# DownLoad.net
KiCad netlist of a schematic drawn in Altium Designer
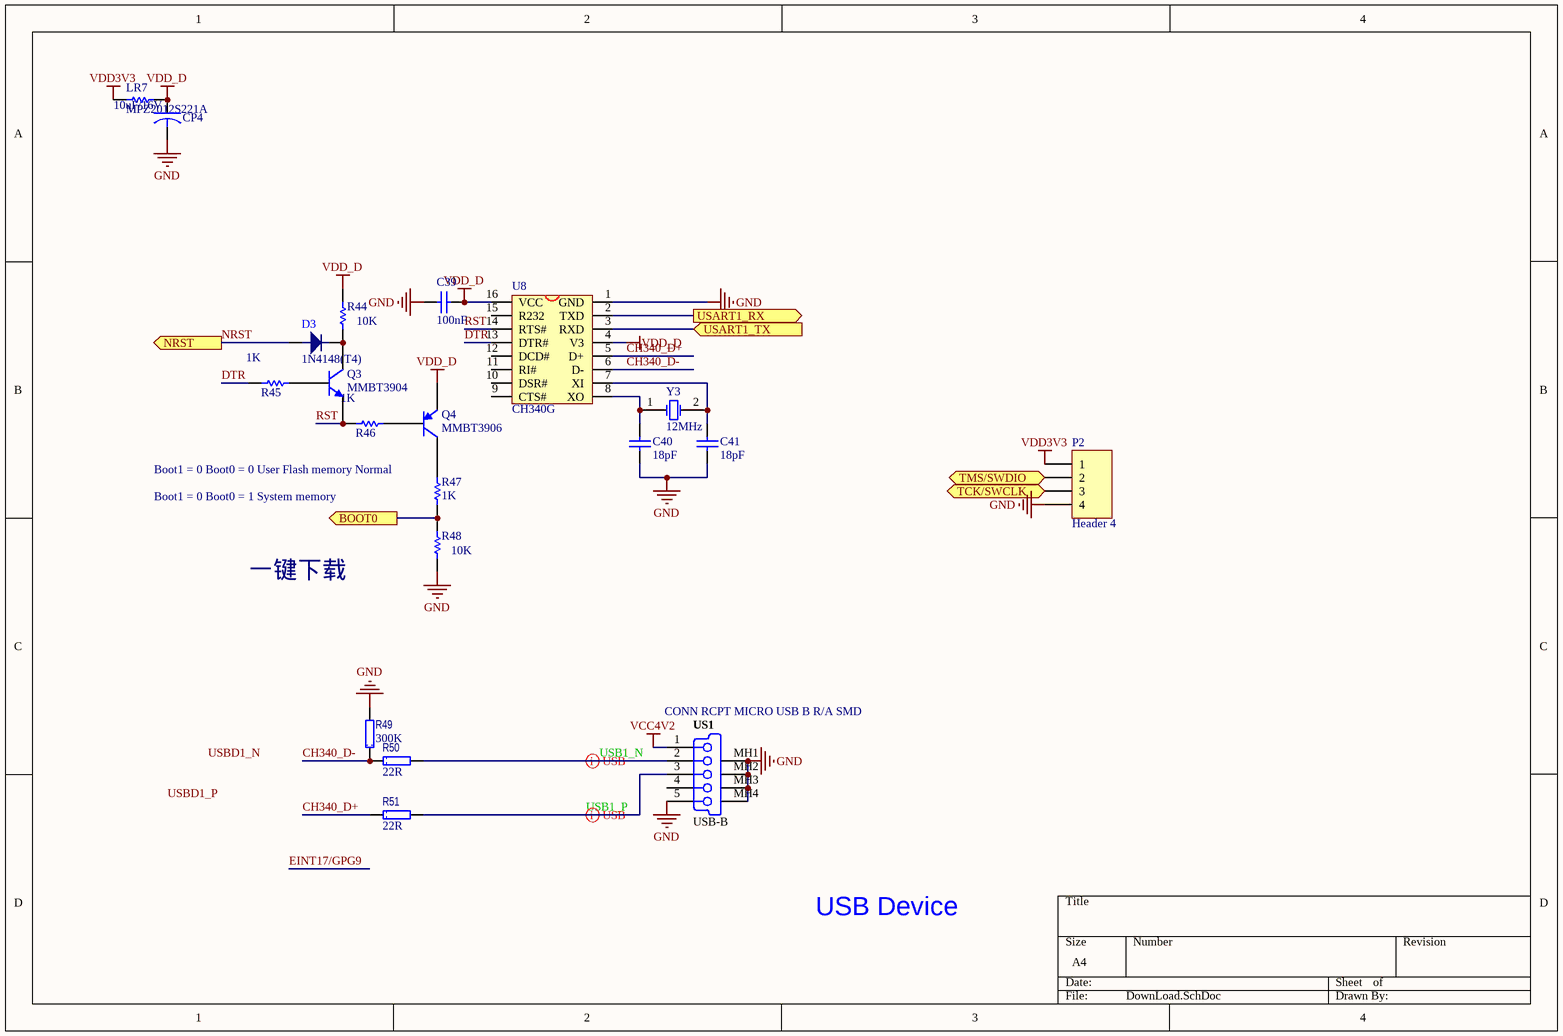
[diagram p0: DownLoad.SchDoc]

(export (version "E")
  (design (tool "Eeschema 10.0.6"))
  (components
    (comp (ref "C39")
      (value "100nF")
      (footprint "2012[0805]06CD")
      (description "CAP 100nF 50V ±5% 0805 (2012 Metric) Thickness 1mm SMD")
      (fields (field (name "TOLERANCE") "±5%") (field (name "Comment") "CAP 100nF 50V 0805(2012)"))
      (libsource (lib "Altium Content Vault") (part "CMP-1036-04418-1"))
    )
    (comp (ref "C40")
      (value "18pF")
      (footprint "2012[0805]100_L")
      (description "CAP 18pF 50V ±1% 0805 (2012 Metric) Thickness 0.75mm SMD")
      (fields (field (name "TOLERANCE") "±1%") (field (name "Comment") "CAP 18pF 50V 0805(2012)"))
      (libsource (lib "Altium Content Vault") (part "CMP-1036-01136-1"))
    )
    (comp (ref "C41")
      (value "18pF")
      (footprint "2012[0805]100_L")
      (description "CAP 18pF 50V ±1% 0805 (2012 Metric) Thickness 0.75mm SMD")
      (fields (field (name "TOLERANCE") "±1%") (field (name "Comment") "CAP 18pF 50V 0805(2012)"))
      (libsource (lib "Altium Content Vault") (part "CMP-1036-01136-1"))
    )
    (comp (ref "CP4")
      (value "10uF/16V")
      (footprint "3216[1206]CB")
      (description "钽质电容器-固体SMD 16volts 10uF 10%")
      (fields (field (name "MANUFACTURER") "AVX") (field (name "MANUFACTURER PART NUMBER") "TAJA106K016RNJ"))
      (libsource (lib "*") (part "CAPACITOR"))
    )
    (comp (ref "D3")
      (value "1N4148(T4)")
      (footprint "SOD123")
      (description "高速开关二极管")
      (libsource (lib "mylib") (part "1N4148"))
    )
    (comp (ref "LR7")
      (value "MPZ2012S221A")
      (footprint "2012[0805]RL")
      (description "电磁干扰滤波珠子、扼流圈和阵列 Ferrite Chip Beads")
      (fields (field (name "MANUFACTURER") "TDK"))
      (libsource (lib "Miscellaneous Devices") (part "Res Semi"))
    )
    (comp (ref "P2")
      (value "Header 4")
      (footprint "HDR1X4")
      (description "Header, 4-Pin")
      (fields (field (name "PUBLISHER") "Altium Limited"))
      (libsource (lib "Miscellaneous Connectors") (part "Header 4"))
    )
    (comp (ref "Q3")
      (value "MMBT3904")
      (footprint "SOT23_N")
      (description "NPN Switching Transistor")
      (fields (field (name "PUBLISHER") "Altium Limited"))
      (libsource (lib "Philips Discrete BJT - Low Power") (part "MMBT3904"))
    )
    (comp (ref "Q4")
      (value "MMBT3906")
      (footprint "SOT23B_N")
      (description "PNP Switching Transistor")
      (fields (field (name "PUBLISHER") "Altium Limited"))
      (libsource (lib "Philips Discrete BJT - Low Power") (part "MMBT3906"))
    )
    (comp (ref "R44")
      (value "10K")
      (footprint "2012[0805]R")
      (description "10K 0.125W 1% 0805 (2012 Metric)  SMD")
      (fields (field (name "TOLERANCE") "1 %") (field (name "POWER") "0.125 W"))
      (libsource (lib "Altium Content Vault") (part "CMP-1013-00623-1"))
    )
    (comp (ref "R45")
      (value "1K")
      (footprint "2012[0805]R")
      (description "1K 0.125W 1% 0805 (2012 Metric)  SMD")
      (fields (field (name "TOLERANCE") "1 %") (field (name "POWER") "0.125 W"))
      (libsource (lib "Altium Content Vault") (part "CMP-1013-00510-1"))
    )
    (comp (ref "R46")
      (value "1K")
      (footprint "2012[0805]R")
      (description "1K 0.125W 1% 0805 (2012 Metric)  SMD")
      (fields (field (name "TOLERANCE") "1 %") (field (name "POWER") "0.125 W"))
      (libsource (lib "Altium Content Vault") (part "CMP-1013-00510-1"))
    )
    (comp (ref "R47")
      (value "1K")
      (footprint "2012[0805]R")
      (description "1K 0.125W 1% 0805 (2012 Metric)  SMD")
      (fields (field (name "TOLERANCE") "1 %") (field (name "POWER") "0.125 W"))
      (libsource (lib "Altium Content Vault") (part "CMP-1013-00510-1"))
    )
    (comp (ref "R48")
      (value "10K")
      (footprint "2012[0805]R")
      (description "10K 0.125W 1% 0805 (2012 Metric)  SMD")
      (fields (field (name "TOLERANCE") "1 %") (field (name "POWER") "0.125 W"))
      (libsource (lib "Altium Content Vault") (part "CMP-1013-00623-1"))
    )
    (comp (ref "R49")
      (value "300K")
      (footprint "2012[0805]R")
      (description "厚膜电阻器 - SMD 1/10watt 300Kohms 1%")
      (fields
        (field (name "MANUFACTURER") "Vishay / Dale")
        (field (name "MANUFACTURER PART NUMBER") "CRCW0603300KFKEA")
      )
      (libsource (lib "300K 1%") (part "RES"))
    )
    (comp (ref "R50")
      (value "22R")
      (footprint "2012[0805]R")
      (description "厚膜电阻器 - SMD 1/10watt 22ohms 1%")
      (fields
        (field (name "MANUFACTURER") "Vishay / Dale")
        (field (name "MANUFACTURER PART NUMBER") "CRCW060322R0FKEA")
      )
      (libsource (lib "22R 1%") (part "RES"))
    )
    (comp (ref "R51")
      (value "22R")
      (footprint "2012[0805]R")
      (description "厚膜电阻器 - SMD 1/10watt 22ohms 1%")
      (fields
        (field (name "MANUFACTURER") "Vishay / Dale")
        (field (name "MANUFACTURER PART NUMBER") "CRCW060322R0FKEA")
      )
      (libsource (lib "22R 1%") (part "RES"))
    )
    (comp (ref "U8")
      (value "CH340G")
      (footprint "SOIC16_N")
      (description "USB2UART")
      (libsource (lib "mylib") (part "CH340G"))
    )
    (comp (ref "US1")
      (value "USB-B")
      (footprint "USB_micro_AB")
      (fields
        (field (name "MANUFACTURER") "TE Connectivity")
        (field (name "MANUFACTURER PART NUMBER") "1981568-1")
        (field (name "DESCRIPTION 1") "CONN RCPT MICRO USB B R/A SMD")
      )
      (libsource (lib "AltiumDesignLibrary") (part "0481900001"))
    )
    (comp (ref "Y3")
      (value "12MHz")
      (footprint "XTAL_HC-49")
      (description "Crystal Oscillator")
      (fields (field (name "PUBLISHER") "Altium Limited"))
      (libsource (lib "mylib") (part "XTAL"))
    )
  )
  (nets
    (net (code "1") (name "/BOOT0") (class "Default")
      (node (ref "R47") (pin "1") (pinfunction "1_1") (pintype "passive"))
      (node (ref "R48") (pin "2") (pinfunction "2_2") (pintype "passive"))
    )
    (net (code "2") (name "/CH340_D+") (class "Default")
      (node (ref "R51") (pin "1") (pinfunction "1_1") (pintype "passive"))
      (node (ref "U8") (pin "5") (pinfunction "D+_5") (pintype "passive"))
    )
    (net (code "3") (name "/CH340_D-") (class "Default")
      (node (ref "R49") (pin "1") (pinfunction "1_1") (pintype "passive"))
      (node (ref "R50") (pin "1") (pinfunction "1_1") (pintype "passive"))
      (node (ref "U8") (pin "6") (pinfunction "D-_6") (pintype "passive"))
    )
    (net (code "4") (name "/DTR") (class "Default")
      (node (ref "R45") (pin "1") (pinfunction "1_1") (pintype "passive"))
      (node (ref "U8") (pin "13") (pinfunction "DTR#_13") (pintype "passive"))
    )
    (net (code "6") (name "/NRST") (class "Default") (node (ref "D3") (pin "1") (pintype "passive")))
    (net (code "7") (name "/RST") (class "Default")
      (node (ref "Q3") (pin "2") (pinfunction "E_2") (pintype "passive"))
      (node (ref "R46") (pin "1") (pinfunction "1_1") (pintype "passive"))
      (node (ref "U8") (pin "14") (pinfunction "RTS#_14") (pintype "passive"))
    )
    (net (code "8") (name "/TCK{slash}SWCLK") (class "Default")
      (node (ref "P2") (pin "3") (pinfunction "3_3") (pintype "passive"))
    )
    (net (code "9") (name "/TMS{slash}SWDIO") (class "Default")
      (node (ref "P2") (pin "2") (pinfunction "2_2") (pintype "passive"))
    )
    (net (code "10") (name "/USART1_RX") (class "Default")
      (node (ref "U8") (pin "2") (pinfunction "TXD_2") (pintype "passive"))
    )
    (net (code "11") (name "/USART1_TX") (class "Default")
      (node (ref "U8") (pin "3") (pinfunction "RXD_3") (pintype "passive"))
    )
    (net (code "12") (name "/USB1_N") (class "Default")
      (node (ref "R50") (pin "2") (pinfunction "2_2") (pintype "passive"))
      (node (ref "US1") (pin "2") (pinfunction "2_2") (pintype "passive"))
    )
    (net (code "13") (name "/USB1_P") (class "Default")
      (node (ref "R51") (pin "2") (pinfunction "2_2") (pintype "passive"))
      (node (ref "US1") (pin "3") (pinfunction "3_3") (pintype "passive"))
    )
    (net (code "16") (name "GND") (class "Default")
      (node (ref "C39") (pin "2") (pinfunction "2_2") (pintype "passive"))
      (node (ref "C40") (pin "2") (pinfunction "2_2") (pintype "passive"))
      (node (ref "C41") (pin "2") (pinfunction "2_2") (pintype "passive"))
      (node (ref "CP4") (pin "2") (pinfunction "2_2") (pintype "passive"))
      (node (ref "P2") (pin "4") (pinfunction "4_4") (pintype "passive"))
      (node (ref "R48") (pin "1") (pinfunction "1_1") (pintype "passive"))
      (node (ref "R49") (pin "2") (pinfunction "2_2") (pintype "passive"))
      (node (ref "U8") (pin "1") (pinfunction "GND_1") (pintype "passive"))
      (node (ref "US1") (pin "5") (pinfunction "5_5") (pintype "passive"))
      (node (ref "US1") (pin "MH1") (pinfunction "MH1_MH1") (pintype "passive"))
      (node (ref "US1") (pin "MH2") (pinfunction "MH2_MH2") (pintype "passive"))
      (node (ref "US1") (pin "MH3") (pinfunction "MH3_MH3") (pintype "passive"))
      (node (ref "US1") (pin "MH4") (pinfunction "MH4_MH4") (pintype "passive"))
    )
    (net (code "17") (name "Net-(Q3-B)") (class "Default")
      (node (ref "Q3") (pin "1") (pinfunction "B_1") (pintype "passive"))
      (node (ref "R45") (pin "2") (pinfunction "2_2") (pintype "passive"))
    )
    (net (code "18") (name "Net-(Q3-C)") (class "Default")
      (node (ref "D3") (pin "2") (pintype "passive"))
      (node (ref "Q3") (pin "3") (pinfunction "C_3") (pintype "passive"))
      (node (ref "R44") (pin "1") (pinfunction "1_1") (pintype "passive"))
    )
    (net (code "19") (name "Net-(Q4-B)") (class "Default")
      (node (ref "Q4") (pin "1") (pinfunction "B_1") (pintype "passive"))
      (node (ref "R46") (pin "2") (pinfunction "2_2") (pintype "passive"))
    )
    (net (code "20") (name "Net-(Q4-C)") (class "Default")
      (node (ref "Q4") (pin "3") (pinfunction "C_3") (pintype "passive"))
      (node (ref "R47") (pin "2") (pinfunction "2_2") (pintype "passive"))
    )
    (net (code "21") (name "Net-(U8-XI)") (class "Default")
      (node (ref "C41") (pin "1") (pinfunction "1_1") (pintype "passive"))
      (node (ref "U8") (pin "7") (pinfunction "XI_7") (pintype "passive"))
      (node (ref "Y3") (pin "2") (pinfunction "OSC2_2") (pintype "passive"))
    )
    (net (code "22") (name "Net-(U8-XO)") (class "Default")
      (node (ref "C40") (pin "1") (pinfunction "1_1") (pintype "passive"))
      (node (ref "U8") (pin "8") (pinfunction "XO_8") (pintype "passive"))
      (node (ref "Y3") (pin "1") (pinfunction "OSC1_1") (pintype "passive"))
    )
    (net (code "23") (name "VCC4V2") (class "Default")
      (node (ref "US1") (pin "1") (pinfunction "1_1") (pintype "passive"))
    )
    (net (code "24") (name "VDD3V3") (class "Default")
      (node (ref "LR7") (pin "1") (pinfunction "1_1") (pintype "passive"))
      (node (ref "P2") (pin "1") (pinfunction "1_1") (pintype "passive"))
    )
    (net (code "25") (name "VDD_D") (class "Default")
      (node (ref "C39") (pin "1") (pinfunction "1_1") (pintype "passive"))
      (node (ref "CP4") (pin "1") (pinfunction "1_1") (pintype "passive"))
      (node (ref "LR7") (pin "2") (pinfunction "2_2") (pintype "passive"))
      (node (ref "Q4") (pin "2") (pinfunction "E_2") (pintype "passive"))
      (node (ref "R44") (pin "2") (pinfunction "2_2") (pintype "passive"))
      (node (ref "U8") (pin "16") (pinfunction "VCC_16") (pintype "passive"))
      (node (ref "U8") (pin "4") (pinfunction "V3_4") (pintype "passive"))
    )
    (net (code "26") (name "unconnected-(U8-CTS#-Pad9)") (class "Default")
      (node (ref "U8") (pin "9") (pinfunction "CTS#_9") (pintype "passive"))
    )
    (net (code "27") (name "unconnected-(U8-DCD#-Pad12)") (class "Default")
      (node (ref "U8") (pin "12") (pinfunction "DCD#_12") (pintype "passive"))
    )
    (net (code "28") (name "unconnected-(U8-DSR#-Pad10)") (class "Default")
      (node (ref "U8") (pin "10") (pinfunction "DSR#_10") (pintype "passive"))
    )
    (net (code "29") (name "unconnected-(U8-R232-Pad15)") (class "Default")
      (node (ref "U8") (pin "15") (pinfunction "R232_15") (pintype "passive"))
    )
    (net (code "30") (name "unconnected-(U8-RI#-Pad11)") (class "Default")
      (node (ref "U8") (pin "11") (pinfunction "RI#_11") (pintype "passive"))
    )
    (net (code "31") (name "unconnected-(US1-Pad4)") (class "Default")
      (node (ref "US1") (pin "4") (pinfunction "4_4") (pintype "passive"))
    )
  )
)
